# ProPrj_usb__2025-12-14-12-34-49.net
KiCad netlist of a schematic drawn in EasyEDA Pro
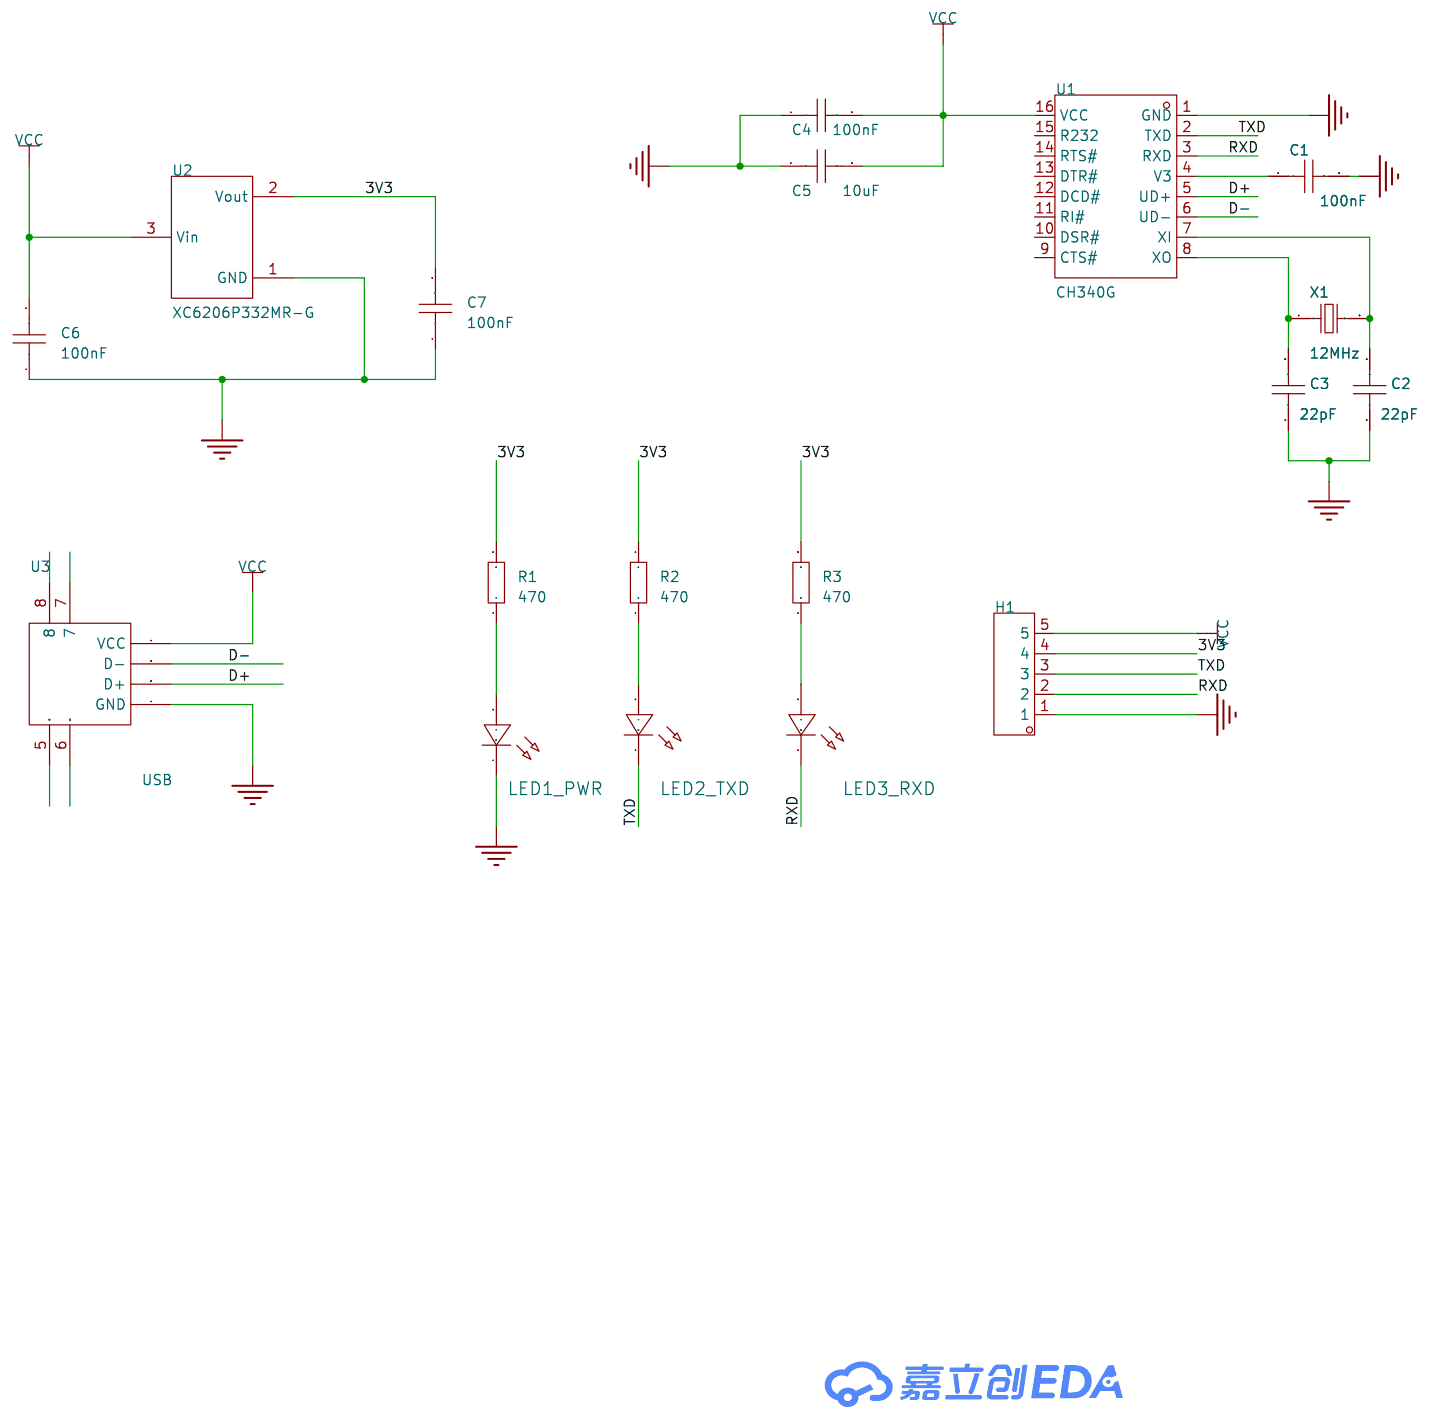
[diagram p0: schematic sheet]

(export (version "E")
  (design (tool "Eeschema 10.0.6"))
  (components
    (comp (ref "C1")
      (value "100nF")
      (footprint "easyedapro:C0603")
      (libsource (lib "easyedapro") (part "Capacitance"))
    )
    (comp (ref "C2")
      (value "22pF")
      (footprint "easyedapro:C0603")
      (libsource (lib "easyedapro") (part "Capacitance"))
    )
    (comp (ref "C3")
      (value "22pF")
      (footprint "easyedapro:C0603")
      (libsource (lib "easyedapro") (part "Capacitance"))
    )
    (comp (ref "C4")
      (value "100nF")
      (footprint "easyedapro:C0603")
      (libsource (lib "easyedapro") (part "Capacitance"))
    )
    (comp (ref "C5")
      (value "10uF")
      (footprint "easyedapro:C0603")
      (libsource (lib "easyedapro") (part "Capacitance"))
    )
    (comp (ref "C6")
      (value "100nF")
      (footprint "easyedapro:C0603")
      (libsource (lib "easyedapro") (part "Capacitance"))
    )
    (comp (ref "C7")
      (value "100nF")
      (footprint "easyedapro:C0603")
      (libsource (lib "easyedapro") (part "Capacitance"))
    )
    (comp (ref "H1")
      (value "~")
      (footprint "easyedapro:HDR-TH_5P-P2.54-V-M")
      (libsource (lib "easyedapro") (part "MTP125-1105S1"))
    )
    (comp (ref "LED1_PWR")
      (value "~")
      (footprint "easyedapro:LED_0603")
      (libsource (lib "easyedapro") (part "LED_R"))
    )
    (comp (ref "LED2_TXD")
      (value "~")
      (footprint "easyedapro:LED_0603")
      (libsource (lib "easyedapro") (part "LED_R"))
    )
    (comp (ref "LED3_RXD")
      (value "~")
      (footprint "easyedapro:LED_0603")
      (libsource (lib "easyedapro") (part "LED_R"))
    )
    (comp (ref "R1") (value "470") (footprint "easyedapro:R0603") (libsource (lib "easyedapro") (part "电阻")))
    (comp (ref "R2") (value "470") (footprint "easyedapro:R0603") (libsource (lib "easyedapro") (part "电阻")))
    (comp (ref "R3") (value "470") (footprint "easyedapro:R0603") (libsource (lib "easyedapro") (part "电阻")))
    (comp (ref "U1")
      (value "CH340G")
      (footprint "easyedapro:SOIC-16_L9.9-W3.9-P1.27-LS6.0-BL")
      (description "应用功能:USB转UART;接口协议:USB 2.0;数据速率:2Mbps;")
      (fields (field (name "Manufacturer") "WCH(南京沁恒)"))
      (libsource (lib "easyedapro") (part "CH340G"))
    )
    (comp (ref "U2")
      (value "XC6206P332MR-G")
      (footprint "easyedapro:SOT-23-3_L2.9-W1.6-P1.90-LS2.8-BR")
      (description "输出类型:固定;工作电压:6V;输出电压:3.3V;输出电流:200mA;电源纹波抑制比(PSRR):-;输出极性:正极;")
      (fields (field (name "Manufacturer") "TOREX(特瑞仕)"))
      (libsource (lib "easyedapro") (part "XC6206P332MR"))
    )
    (comp (ref "U3")
      (value "USB")
      (footprint "easyedapro:USB-SMD_USB_1")
      (libsource (lib "easyedapro") (part "USB"))
    )
    (comp (ref "X1")
      (value "12MHz")
      (footprint "easyedapro:CRYSTAL-SMD_L5.0-W3.2")
      (description "晶振类型:贴片晶振;频率:12MHz;常温频差:±20ppm;负载电容:20pF;频率稳定度:±30ppm;")
      (fields
        (field (name "Manufacturer Part") "XC53G2-12.000-F20LJDT")
        (field (name "Manufacturer") "HCI(杭晶)")
      )
      (libsource (lib "easyedapro") (part "XC53G2-12.000-F20LJDT"))
    )
  )
  (nets
    (net (code "1") (name "/3V3") (class "Default")
      (node (ref "C7") (pin "2") (pinfunction "2_2") (pintype "input"))
      (node (ref "H1") (pin "4") (pinfunction "4_4") (pintype "unspecified"))
      (node (ref "R1") (pin "2") (pinfunction "2_2") (pintype "input"))
      (node (ref "R2") (pin "2") (pinfunction "2_2") (pintype "input"))
      (node (ref "R3") (pin "2") (pinfunction "2_2") (pintype "input"))
      (node (ref "U2") (pin "2") (pinfunction "Vout_2") (pintype "unspecified"))
    )
    (net (code "2") (name "/D+") (class "Default")
      (node (ref "U1") (pin "5") (pinfunction "UD+_5") (pintype "unspecified"))
      (node (ref "U3") (pin "3") (pinfunction "D+_3") (pintype "input"))
    )
    (net (code "3") (name "/D-") (class "Default")
      (node (ref "U1") (pin "6") (pinfunction "UD-_6") (pintype "unspecified"))
      (node (ref "U3") (pin "2") (pinfunction "D-_2") (pintype "input"))
    )
    (net (code "4") (name "/RXD") (class "Default")
      (node (ref "H1") (pin "2") (pinfunction "2_2") (pintype "unspecified"))
      (node (ref "LED3_RXD") (pin "1") (pinfunction "C_1") (pintype "input"))
      (node (ref "U1") (pin "3") (pinfunction "RXD_3") (pintype "unspecified"))
    )
    (net (code "5") (name "/TXD") (class "Default")
      (node (ref "H1") (pin "3") (pinfunction "3_3") (pintype "unspecified"))
      (node (ref "LED2_TXD") (pin "1") (pinfunction "C_1") (pintype "input"))
      (node (ref "U1") (pin "2") (pinfunction "TXD_2") (pintype "unspecified"))
    )
    (net (code "6") (name "GND") (class "Default")
      (node (ref "C1") (pin "2") (pinfunction "2_2") (pintype "input"))
      (node (ref "C2") (pin "1") (pinfunction "1_1") (pintype "input"))
      (node (ref "C3") (pin "1") (pinfunction "1_1") (pintype "input"))
      (node (ref "C4") (pin "1") (pinfunction "1_1") (pintype "input"))
      (node (ref "C5") (pin "1") (pinfunction "1_1") (pintype "input"))
      (node (ref "C6") (pin "1") (pinfunction "1_1") (pintype "input"))
      (node (ref "C7") (pin "1") (pinfunction "1_1") (pintype "input"))
      (node (ref "H1") (pin "1") (pinfunction "1_1") (pintype "unspecified"))
      (node (ref "LED1_PWR") (pin "1") (pinfunction "C_1") (pintype "input"))
      (node (ref "U1") (pin "1") (pinfunction "GND_1") (pintype "unspecified"))
      (node (ref "U2") (pin "1") (pinfunction "GND_1") (pintype "unspecified"))
      (node (ref "U3") (pin "4") (pinfunction "GND_4") (pintype "input"))
    )
    (net (code "7") (name "Net-(LED1_PWR-A)") (class "Default")
      (node (ref "LED1_PWR") (pin "2") (pinfunction "A_2") (pintype "input"))
      (node (ref "R1") (pin "1") (pinfunction "1_1") (pintype "input"))
    )
    (net (code "8") (name "Net-(LED2_TXD-A)") (class "Default")
      (node (ref "LED2_TXD") (pin "2") (pinfunction "A_2") (pintype "input"))
      (node (ref "R2") (pin "1") (pinfunction "1_1") (pintype "input"))
    )
    (net (code "9") (name "Net-(LED3_RXD-A)") (class "Default")
      (node (ref "LED3_RXD") (pin "2") (pinfunction "A_2") (pintype "input"))
      (node (ref "R3") (pin "1") (pinfunction "1_1") (pintype "input"))
    )
    (net (code "10") (name "Net-(U1-V3)") (class "Default")
      (node (ref "C1") (pin "1") (pinfunction "1_1") (pintype "input"))
      (node (ref "U1") (pin "4") (pinfunction "V3_4") (pintype "unspecified"))
    )
    (net (code "11") (name "Net-(U1-XI)") (class "Default")
      (node (ref "C2") (pin "2") (pinfunction "2_2") (pintype "input"))
      (node (ref "U1") (pin "7") (pinfunction "XI_7") (pintype "unspecified"))
      (node (ref "X1") (pin "2") (pinfunction "2_2") (pintype "unspecified"))
    )
    (net (code "12") (name "Net-(U1-XO)") (class "Default")
      (node (ref "C3") (pin "2") (pinfunction "2_2") (pintype "input"))
      (node (ref "U1") (pin "8") (pinfunction "XO_8") (pintype "unspecified"))
      (node (ref "X1") (pin "1") (pinfunction "1_1") (pintype "unspecified"))
    )
    (net (code "13") (name "VCC") (class "Default")
      (node (ref "C4") (pin "2") (pinfunction "2_2") (pintype "input"))
      (node (ref "C5") (pin "2") (pinfunction "2_2") (pintype "input"))
      (node (ref "C6") (pin "2") (pinfunction "2_2") (pintype "input"))
      (node (ref "H1") (pin "5") (pinfunction "5_5") (pintype "unspecified"))
      (node (ref "U1") (pin "16") (pinfunction "VCC_16") (pintype "unspecified"))
      (node (ref "U2") (pin "3") (pinfunction "Vin_3") (pintype "unspecified"))
      (node (ref "U3") (pin "1") (pinfunction "VCC_1") (pintype "input"))
    )
    (net (code "14") (name "unconnected-(U1-CTS#-Pad9)") (class "Default")
      (node (ref "U1") (pin "9") (pinfunction "CTS#_9") (pintype "unspecified"))
    )
    (net (code "15") (name "unconnected-(U1-DCD#-Pad12)") (class "Default")
      (node (ref "U1") (pin "12") (pinfunction "DCD#_12") (pintype "unspecified"))
    )
    (net (code "16") (name "unconnected-(U1-DSR#-Pad10)") (class "Default")
      (node (ref "U1") (pin "10") (pinfunction "DSR#_10") (pintype "unspecified"))
    )
    (net (code "17") (name "unconnected-(U1-DTR#-Pad13)") (class "Default")
      (node (ref "U1") (pin "13") (pinfunction "DTR#_13") (pintype "unspecified"))
    )
    (net (code "18") (name "unconnected-(U1-R232-Pad15)") (class "Default")
      (node (ref "U1") (pin "15") (pinfunction "R232_15") (pintype "unspecified"))
    )
    (net (code "19") (name "unconnected-(U1-RI#-Pad11)") (class "Default")
      (node (ref "U1") (pin "11") (pinfunction "RI#_11") (pintype "unspecified"))
    )
    (net (code "20") (name "unconnected-(U1-RTS#-Pad14)") (class "Default")
      (node (ref "U1") (pin "14") (pinfunction "RTS#_14") (pintype "unspecified"))
    )
    (net (code "21") (name "unconnected-(U3-Pad7)") (class "Default")
      (node (ref "U3") (pin "7") (pinfunction "7_7") (pintype "unspecified"))
    )
    (net (code "22") (name "unconnected-(U3-Pad8)") (class "Default")
      (node (ref "U3") (pin "8") (pinfunction "8_8") (pintype "unspecified"))
    )
    (net (code "23") (name "unconnected-(U3-SH1-Pad5)") (class "Default")
      (node (ref "U3") (pin "5") (pinfunction "SH1_5") (pintype "unspecified"))
    )
    (net (code "24") (name "unconnected-(U3-SH2-Pad6)") (class "Default")
      (node (ref "U3") (pin "6") (pinfunction "SH2_6") (pintype "unspecified"))
    )
  )
)
